# FINGER_CONNECTORS.net
KiCad netlist of a schematic drawn in Altium Designer
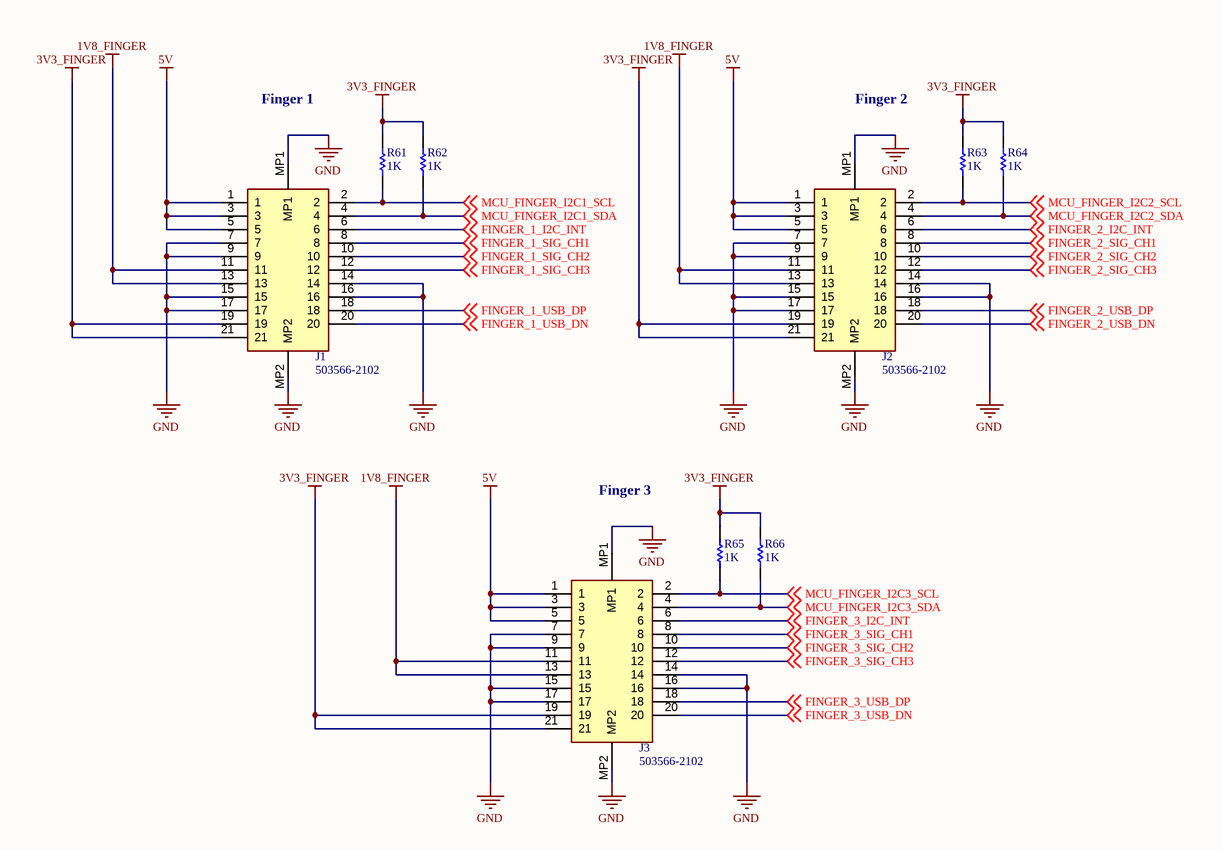
[diagram p0: FINGER_CONNECTORS.SchDoc]

(export (version "E")
  (design (tool "Eeschema 10.0.6"))
  (components
    (comp (ref "J1")
      (value "503566-2102")
      (footprint "SamacSys:5035662102")
      (description "Connector")
      (fields (field (name "MOUSER PART NUMBER") "538-503566-2102"))
      (libsource (lib "*") (part "503566-2102"))
    )
    (comp (ref "J2")
      (value "503566-2102")
      (footprint "SamacSys:5035662102")
      (description "Connector")
      (fields (field (name "MOUSER PART NUMBER") "538-503566-2102"))
      (libsource (lib "*") (part "503566-2102"))
    )
    (comp (ref "J3")
      (value "503566-2102")
      (footprint "SamacSys:5035662102")
      (description "Connector")
      (fields (field (name "MOUSER PART NUMBER") "538-503566-2102"))
      (libsource (lib "*") (part "503566-2102"))
    )
    (comp (ref "R61")
      (value "1K")
      (footprint "RESC1005X40X25LL05T10")
      (fields (field (name "PART NUMBER") "RC0402JR-071KL") (field (name "MANUFACTURER") "Yageo / Phycomp"))
      (libsource (lib "Altium Content Vault") (part "RES"))
    )
    (comp (ref "R62")
      (value "1K")
      (footprint "RESC1005X40X25LL05T10")
      (fields (field (name "PART NUMBER") "RC0402JR-071KL") (field (name "MANUFACTURER") "Yageo / Phycomp"))
      (libsource (lib "Altium Content Vault") (part "RES"))
    )
    (comp (ref "R63")
      (value "1K")
      (footprint "RESC1005X40X25LL05T10")
      (fields (field (name "PART NUMBER") "RC0402JR-071KL") (field (name "MANUFACTURER") "Yageo / Phycomp"))
      (libsource (lib "Altium Content Vault") (part "RES"))
    )
    (comp (ref "R64")
      (value "1K")
      (footprint "RESC1005X40X25LL05T10")
      (fields (field (name "PART NUMBER") "RC0402JR-071KL") (field (name "MANUFACTURER") "Yageo / Phycomp"))
      (libsource (lib "Altium Content Vault") (part "RES"))
    )
    (comp (ref "R65")
      (value "1K")
      (footprint "RESC1005X40X25LL05T10")
      (fields (field (name "PART NUMBER") "RC0402JR-071KL") (field (name "MANUFACTURER") "Yageo / Phycomp"))
      (libsource (lib "Altium Content Vault") (part "RES"))
    )
    (comp (ref "R66")
      (value "1K")
      (footprint "RESC1005X40X25LL05T10")
      (fields (field (name "PART NUMBER") "RC0402JR-071KL") (field (name "MANUFACTURER") "Yageo / Phycomp"))
      (libsource (lib "Altium Content Vault") (part "RES"))
    )
  )
  (nets
    (net (code "1") (name "1V8_FINGER") (class "Default")
      (node (ref "J1") (pin "11") (pinfunction "11_11") (pintype "passive"))
      (node (ref "J1") (pin "13") (pinfunction "13_13") (pintype "passive"))
      (node (ref "J2") (pin "11") (pinfunction "11_11") (pintype "passive"))
      (node (ref "J2") (pin "13") (pinfunction "13_13") (pintype "passive"))
      (node (ref "J3") (pin "11") (pinfunction "11_11") (pintype "passive"))
      (node (ref "J3") (pin "13") (pinfunction "13_13") (pintype "passive"))
    )
    (net (code "2") (name "3V3_FINGER") (class "Default")
      (node (ref "J1") (pin "19") (pinfunction "19_19") (pintype "passive"))
      (node (ref "J1") (pin "21") (pinfunction "21_21") (pintype "passive"))
      (node (ref "J2") (pin "19") (pinfunction "19_19") (pintype "passive"))
      (node (ref "J2") (pin "21") (pinfunction "21_21") (pintype "passive"))
      (node (ref "J3") (pin "19") (pinfunction "19_19") (pintype "passive"))
      (node (ref "J3") (pin "21") (pinfunction "21_21") (pintype "passive"))
      (node (ref "R61") (pin "2") (pinfunction "2_2") (pintype "passive"))
      (node (ref "R62") (pin "2") (pinfunction "2_2") (pintype "passive"))
      (node (ref "R63") (pin "2") (pinfunction "2_2") (pintype "passive"))
      (node (ref "R64") (pin "2") (pinfunction "2_2") (pintype "passive"))
      (node (ref "R65") (pin "2") (pinfunction "2_2") (pintype "passive"))
      (node (ref "R66") (pin "2") (pinfunction "2_2") (pintype "passive"))
    )
    (net (code "3") (name "5V") (class "Default")
      (node (ref "J1") (pin "1") (pinfunction "1_1") (pintype "passive"))
      (node (ref "J1") (pin "3") (pinfunction "3_3") (pintype "passive"))
      (node (ref "J1") (pin "5") (pinfunction "5_5") (pintype "passive"))
      (node (ref "J2") (pin "1") (pinfunction "1_1") (pintype "passive"))
      (node (ref "J2") (pin "3") (pinfunction "3_3") (pintype "passive"))
      (node (ref "J2") (pin "5") (pinfunction "5_5") (pintype "passive"))
      (node (ref "J3") (pin "1") (pinfunction "1_1") (pintype "passive"))
      (node (ref "J3") (pin "3") (pinfunction "3_3") (pintype "passive"))
      (node (ref "J3") (pin "5") (pinfunction "5_5") (pintype "passive"))
    )
    (net (code "4") (name "FINGER_1_I2C_INT") (class "Default")
      (node (ref "J1") (pin "6") (pinfunction "6_6") (pintype "passive"))
    )
    (net (code "5") (name "FINGER_1_SIG_CH1") (class "Default")
      (node (ref "J1") (pin "8") (pinfunction "8_8") (pintype "passive"))
    )
    (net (code "6") (name "FINGER_1_SIG_CH2") (class "Default")
      (node (ref "J1") (pin "10") (pinfunction "10_10") (pintype "passive"))
    )
    (net (code "7") (name "FINGER_1_SIG_CH3") (class "Default")
      (node (ref "J1") (pin "12") (pinfunction "12_12") (pintype "passive"))
    )
    (net (code "8") (name "FINGER_1_USB_DN") (class "Default")
      (node (ref "J1") (pin "20") (pinfunction "20_20") (pintype "passive"))
    )
    (net (code "9") (name "FINGER_1_USB_DP") (class "Default")
      (node (ref "J1") (pin "18") (pinfunction "18_18") (pintype "passive"))
    )
    (net (code "10") (name "FINGER_2_I2C_INT") (class "Default")
      (node (ref "J2") (pin "6") (pinfunction "6_6") (pintype "passive"))
    )
    (net (code "11") (name "FINGER_2_SIG_CH1") (class "Default")
      (node (ref "J2") (pin "8") (pinfunction "8_8") (pintype "passive"))
    )
    (net (code "12") (name "FINGER_2_SIG_CH2") (class "Default")
      (node (ref "J2") (pin "10") (pinfunction "10_10") (pintype "passive"))
    )
    (net (code "13") (name "FINGER_2_SIG_CH3") (class "Default")
      (node (ref "J2") (pin "12") (pinfunction "12_12") (pintype "passive"))
    )
    (net (code "14") (name "FINGER_2_USB_DN") (class "Default")
      (node (ref "J2") (pin "20") (pinfunction "20_20") (pintype "passive"))
    )
    (net (code "15") (name "FINGER_2_USB_DP") (class "Default")
      (node (ref "J2") (pin "18") (pinfunction "18_18") (pintype "passive"))
    )
    (net (code "16") (name "FINGER_3_I2C_INT") (class "Default")
      (node (ref "J3") (pin "6") (pinfunction "6_6") (pintype "passive"))
    )
    (net (code "17") (name "FINGER_3_SIG_CH1") (class "Default")
      (node (ref "J3") (pin "8") (pinfunction "8_8") (pintype "passive"))
    )
    (net (code "18") (name "FINGER_3_SIG_CH2") (class "Default")
      (node (ref "J3") (pin "10") (pinfunction "10_10") (pintype "passive"))
    )
    (net (code "19") (name "FINGER_3_SIG_CH3") (class "Default")
      (node (ref "J3") (pin "12") (pinfunction "12_12") (pintype "passive"))
    )
    (net (code "20") (name "FINGER_3_USB_DN") (class "Default")
      (node (ref "J3") (pin "20") (pinfunction "20_20") (pintype "passive"))
    )
    (net (code "21") (name "FINGER_3_USB_DP") (class "Default")
      (node (ref "J3") (pin "18") (pinfunction "18_18") (pintype "passive"))
    )
    (net (code "22") (name "GND") (class "Default")
      (node (ref "J1") (pin "14") (pinfunction "14_14") (pintype "passive"))
      (node (ref "J1") (pin "15") (pinfunction "15_15") (pintype "passive"))
      (node (ref "J1") (pin "16") (pinfunction "16_16") (pintype "passive"))
      (node (ref "J1") (pin "17") (pinfunction "17_17") (pintype "passive"))
      (node (ref "J1") (pin "7") (pinfunction "7_7") (pintype "passive"))
      (node (ref "J1") (pin "9") (pinfunction "9_9") (pintype "passive"))
      (node (ref "J1") (pin "MP1") (pinfunction "MP1_MP1") (pintype "passive"))
      (node (ref "J1") (pin "MP2") (pinfunction "MP2_MP2") (pintype "passive"))
      (node (ref "J2") (pin "14") (pinfunction "14_14") (pintype "passive"))
      (node (ref "J2") (pin "15") (pinfunction "15_15") (pintype "passive"))
      (node (ref "J2") (pin "16") (pinfunction "16_16") (pintype "passive"))
      (node (ref "J2") (pin "17") (pinfunction "17_17") (pintype "passive"))
      (node (ref "J2") (pin "7") (pinfunction "7_7") (pintype "passive"))
      (node (ref "J2") (pin "9") (pinfunction "9_9") (pintype "passive"))
      (node (ref "J2") (pin "MP1") (pinfunction "MP1_MP1") (pintype "passive"))
      (node (ref "J2") (pin "MP2") (pinfunction "MP2_MP2") (pintype "passive"))
      (node (ref "J3") (pin "14") (pinfunction "14_14") (pintype "passive"))
      (node (ref "J3") (pin "15") (pinfunction "15_15") (pintype "passive"))
      (node (ref "J3") (pin "16") (pinfunction "16_16") (pintype "passive"))
      (node (ref "J3") (pin "17") (pinfunction "17_17") (pintype "passive"))
      (node (ref "J3") (pin "7") (pinfunction "7_7") (pintype "passive"))
      (node (ref "J3") (pin "9") (pinfunction "9_9") (pintype "passive"))
      (node (ref "J3") (pin "MP1") (pinfunction "MP1_MP1") (pintype "passive"))
      (node (ref "J3") (pin "MP2") (pinfunction "MP2_MP2") (pintype "passive"))
    )
    (net (code "23") (name "MCU_FINGER_I2C1_SCL") (class "Default")
      (node (ref "J1") (pin "2") (pinfunction "2_2") (pintype "passive"))
      (node (ref "R61") (pin "1") (pinfunction "1_1") (pintype "passive"))
    )
    (net (code "24") (name "MCU_FINGER_I2C1_SDA") (class "Default")
      (node (ref "J1") (pin "4") (pinfunction "4_4") (pintype "passive"))
      (node (ref "R62") (pin "1") (pinfunction "1_1") (pintype "passive"))
    )
    (net (code "25") (name "MCU_FINGER_I2C2_SCL") (class "Default")
      (node (ref "J2") (pin "2") (pinfunction "2_2") (pintype "passive"))
      (node (ref "R63") (pin "1") (pinfunction "1_1") (pintype "passive"))
    )
    (net (code "26") (name "MCU_FINGER_I2C2_SDA") (class "Default")
      (node (ref "J2") (pin "4") (pinfunction "4_4") (pintype "passive"))
      (node (ref "R64") (pin "1") (pinfunction "1_1") (pintype "passive"))
    )
    (net (code "27") (name "MCU_FINGER_I2C3_SCL") (class "Default")
      (node (ref "J3") (pin "2") (pinfunction "2_2") (pintype "passive"))
      (node (ref "R65") (pin "1") (pinfunction "1_1") (pintype "passive"))
    )
    (net (code "28") (name "MCU_FINGER_I2C3_SDA") (class "Default")
      (node (ref "J3") (pin "4") (pinfunction "4_4") (pintype "passive"))
      (node (ref "R66") (pin "1") (pinfunction "1_1") (pintype "passive"))
    )
  )
)
